# canmultitap.net
KiCad netlist of a schematic drawn in EAGLE
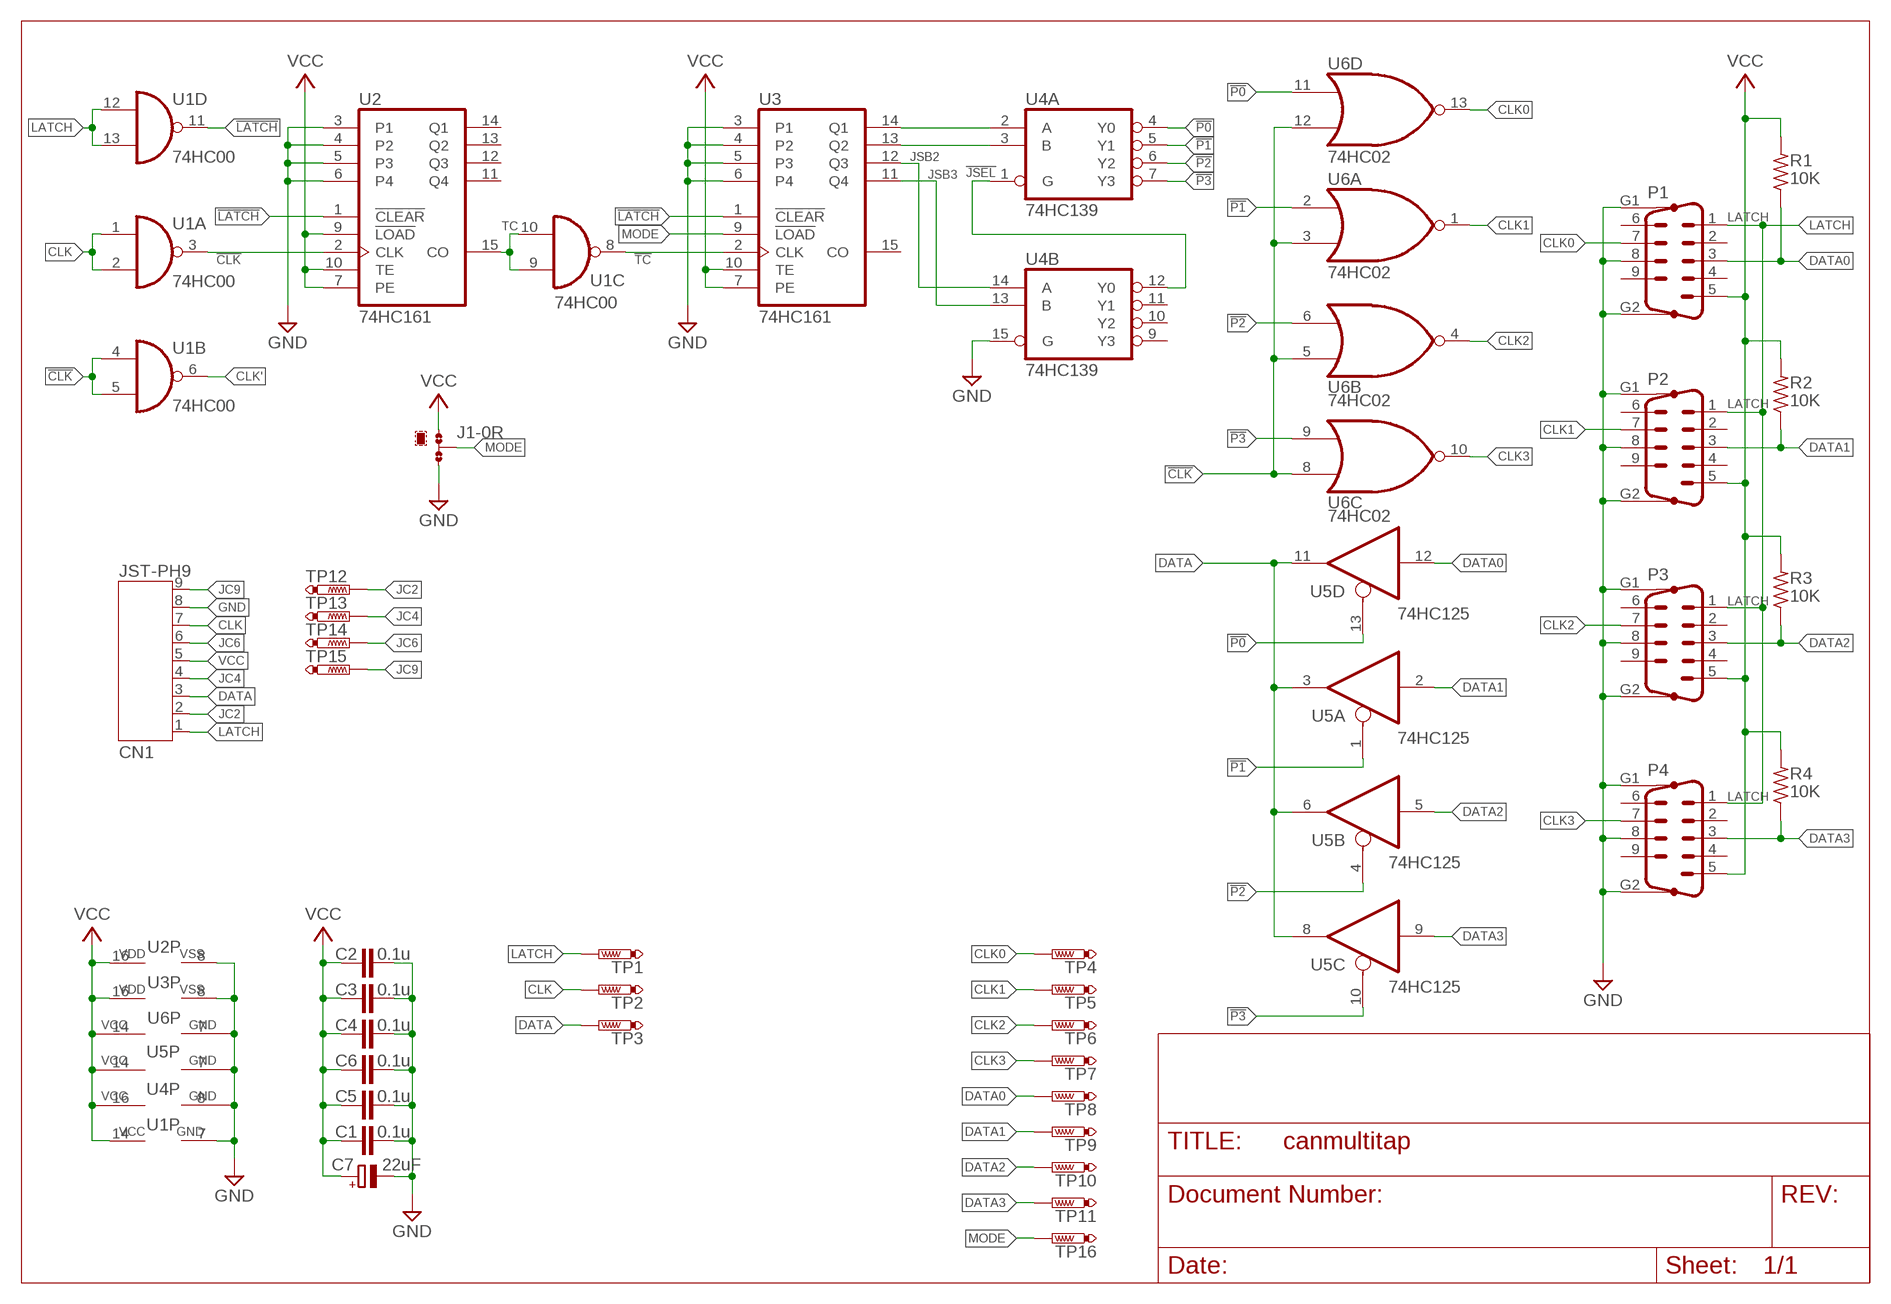
[diagram p0: schematic, sheet 1]

(export (version "E")
  (design (tool "Eeschema 10.0.6"))
  (components
    (comp (ref "C1")
      (value "0.1u")
      (footprint "eagle-import:C0805")
      (libsource (lib "eagle-import") (part "C-EUC0805"))
    )
    (comp (ref "C2")
      (value "0.1u")
      (footprint "eagle-import:C0805")
      (libsource (lib "eagle-import") (part "C-EUC0805"))
    )
    (comp (ref "C3")
      (value "0.1u")
      (footprint "eagle-import:C0805")
      (libsource (lib "eagle-import") (part "C-EUC0805"))
    )
    (comp (ref "C4")
      (value "0.1u")
      (footprint "eagle-import:C0805")
      (libsource (lib "eagle-import") (part "C-EUC0805"))
    )
    (comp (ref "C5")
      (value "0.1u")
      (footprint "eagle-import:C0805")
      (libsource (lib "eagle-import") (part "C-EUC0805"))
    )
    (comp (ref "C6")
      (value "0.1u")
      (footprint "eagle-import:C0805")
      (libsource (lib "eagle-import") (part "C-EUC0805"))
    )
    (comp (ref "C7")
      (value "22uF")
      (footprint "eagle-import:E2-4")
      (libsource (lib "eagle-import") (part "CPOL-EUE2-4"))
    )
    (comp (ref "CN1")
      (value "JST-PH9")
      (footprint "eagle-import:JST-PH9")
      (libsource (lib "eagle-import") (part "JST-PH9"))
    )
    (comp (ref "J1")
      (value "0R-JUMPA")
      (footprint "eagle-import:A0R-JMP")
      (libsource (lib "eagle-import") (part "0R-JUMPA"))
    )
    (comp (ref "P1")
      (value "M09HP")
      (footprint "eagle-import:M09HP")
      (libsource (lib "eagle-import") (part "M09HP"))
    )
    (comp (ref "P2")
      (value "M09HP")
      (footprint "eagle-import:M09HP")
      (libsource (lib "eagle-import") (part "M09HP"))
    )
    (comp (ref "P3")
      (value "M09HP")
      (footprint "eagle-import:M09HP")
      (libsource (lib "eagle-import") (part "M09HP"))
    )
    (comp (ref "P4")
      (value "M09HP")
      (footprint "eagle-import:M09HP")
      (libsource (lib "eagle-import") (part "M09HP"))
    )
    (comp (ref "R1")
      (value "10K")
      (footprint "eagle-import:R0805")
      (libsource (lib "eagle-import") (part "R-US_R0805"))
    )
    (comp (ref "R2")
      (value "10K")
      (footprint "eagle-import:R0805")
      (libsource (lib "eagle-import") (part "R-US_R0805"))
    )
    (comp (ref "R3")
      (value "10K")
      (footprint "eagle-import:R0805")
      (libsource (lib "eagle-import") (part "R-US_R0805"))
    )
    (comp (ref "R4")
      (value "10K")
      (footprint "eagle-import:R0805")
      (libsource (lib "eagle-import") (part "R-US_R0805"))
    )
    (comp (ref "TP1")
      (value "PTR1TP09R")
      (footprint "eagle-import:TP09R")
      (libsource (lib "eagle-import") (part "PTR1TP09R"))
    )
    (comp (ref "TP2")
      (value "PTR1TP09R")
      (footprint "eagle-import:TP09R")
      (libsource (lib "eagle-import") (part "PTR1TP09R"))
    )
    (comp (ref "TP3")
      (value "PTR1TP09R")
      (footprint "eagle-import:TP09R")
      (libsource (lib "eagle-import") (part "PTR1TP09R"))
    )
    (comp (ref "TP4")
      (value "PTR1TP09R")
      (footprint "eagle-import:TP09R")
      (libsource (lib "eagle-import") (part "PTR1TP09R"))
    )
    (comp (ref "TP5")
      (value "PTR1TP09R")
      (footprint "eagle-import:TP09R")
      (libsource (lib "eagle-import") (part "PTR1TP09R"))
    )
    (comp (ref "TP6")
      (value "PTR1TP09R")
      (footprint "eagle-import:TP09R")
      (libsource (lib "eagle-import") (part "PTR1TP09R"))
    )
    (comp (ref "TP7")
      (value "PTR1TP09R")
      (footprint "eagle-import:TP09R")
      (libsource (lib "eagle-import") (part "PTR1TP09R"))
    )
    (comp (ref "TP8")
      (value "PTR1TP09R")
      (footprint "eagle-import:TP09R")
      (libsource (lib "eagle-import") (part "PTR1TP09R"))
    )
    (comp (ref "TP9")
      (value "PTR1TP09R")
      (footprint "eagle-import:TP09R")
      (libsource (lib "eagle-import") (part "PTR1TP09R"))
    )
    (comp (ref "TP10")
      (value "PTR1TP09R")
      (footprint "eagle-import:TP09R")
      (libsource (lib "eagle-import") (part "PTR1TP09R"))
    )
    (comp (ref "TP11")
      (value "PTR1TP09R")
      (footprint "eagle-import:TP09R")
      (libsource (lib "eagle-import") (part "PTR1TP09R"))
    )
    (comp (ref "TP12")
      (value "PTR1TP09R")
      (footprint "eagle-import:TP09R")
      (libsource (lib "eagle-import") (part "PTR1TP09R"))
    )
    (comp (ref "TP13")
      (value "PTR1TP09R")
      (footprint "eagle-import:TP09R")
      (libsource (lib "eagle-import") (part "PTR1TP09R"))
    )
    (comp (ref "TP14")
      (value "PTR1TP09R")
      (footprint "eagle-import:TP09R")
      (libsource (lib "eagle-import") (part "PTR1TP09R"))
    )
    (comp (ref "TP15")
      (value "PTR1TP09R")
      (footprint "eagle-import:TP09R")
      (libsource (lib "eagle-import") (part "PTR1TP09R"))
    )
    (comp (ref "TP16")
      (value "PTR1TP09R")
      (footprint "eagle-import:TP09R")
      (libsource (lib "eagle-import") (part "PTR1TP09R"))
    )
    (comp (ref "U1")
      (value "74HC00")
      (footprint "eagle-import:TSSOP14")
      (libsource (lib "eagle-import") (part "7400PW"))
    )
    (comp (ref "U2")
      (value "74HC161")
      (footprint "eagle-import:TSSOP16")
      (libsource (lib "eagle-import") (part "4161PW"))
    )
    (comp (ref "U3")
      (value "74HC161")
      (footprint "eagle-import:TSSOP16")
      (libsource (lib "eagle-import") (part "4161PW"))
    )
    (comp (ref "U4")
      (value "74HC139")
      (footprint "eagle-import:TSSOP16")
      (libsource (lib "eagle-import") (part "74139PW"))
    )
    (comp (ref "U5")
      (value "74HC125")
      (footprint "eagle-import:TSSOP14")
      (libsource (lib "eagle-import") (part "74125PWABT"))
    )
    (comp (ref "U6")
      (value "74HC02")
      (footprint "eagle-import:TSSOP14")
      (libsource (lib "eagle-import") (part "7402PW"))
    )
  )
  (nets
    (net (code "1") (name "/JSB2") (class "Default")
      (node (ref "U3") (pin "12") (pinfunction "Q3_12") (pintype "output"))
      (node (ref "U4") (pin "14") (pinfunction "A_14") (pintype "input"))
    )
    (net (code "2") (name "/JSB3") (class "Default")
      (node (ref "U3") (pin "11") (pinfunction "Q4_11") (pintype "output"))
      (node (ref "U4") (pin "13") (pinfunction "B_13") (pintype "input"))
    )
    (net (code "3") (name "/TC") (class "Default")
      (node (ref "U1") (pin "10") (pinfunction "I1_10") (pintype "input"))
      (node (ref "U1") (pin "9") (pinfunction "I0_9") (pintype "input"))
      (node (ref "U2") (pin "15") (pinfunction "CO_15") (pintype "output"))
    )
    (net (code "4") (name "/~{CLK}") (class "Default")
      (node (ref "U1") (pin "3") (pinfunction "O_3") (pintype "output"))
      (node (ref "U1") (pin "4") (pinfunction "I0_4") (pintype "input"))
      (node (ref "U1") (pin "5") (pinfunction "I1_5") (pintype "input"))
      (node (ref "U2") (pin "2") (pinfunction "CLK_2") (pintype "input"))
      (node (ref "U6") (pin "12") (pinfunction "I1_12") (pintype "input"))
      (node (ref "U6") (pin "3") (pinfunction "I1_3") (pintype "input"))
      (node (ref "U6") (pin "5") (pinfunction "I0_5") (pintype "input"))
      (node (ref "U6") (pin "8") (pinfunction "I0_8") (pintype "input"))
    )
    (net (code "5") (name "/~{JSEL}") (class "Default")
      (node (ref "U4") (pin "1") (pinfunction "G_1") (pintype "input"))
      (node (ref "U4") (pin "12") (pinfunction "Y0_12") (pintype "output"))
    )
    (net (code "6") (name "/~{LATCH}") (class "Default")
      (node (ref "U1") (pin "11") (pinfunction "O_11") (pintype "output"))
      (node (ref "U2") (pin "1") (pinfunction "~{CLEAR}_1") (pintype "input"))
      (node (ref "U3") (pin "1") (pinfunction "~{CLEAR}_1") (pintype "input"))
    )
    (net (code "7") (name "/~{P0}") (class "Default")
      (node (ref "U4") (pin "4") (pinfunction "Y0_4") (pintype "output"))
      (node (ref "U5") (pin "13") (pinfunction "OE_13") (pintype "input"))
      (node (ref "U6") (pin "11") (pinfunction "I0_11") (pintype "input"))
    )
    (net (code "8") (name "/~{P1}") (class "Default")
      (node (ref "U4") (pin "5") (pinfunction "Y1_5") (pintype "output"))
      (node (ref "U5") (pin "1") (pinfunction "OE_1") (pintype "input"))
      (node (ref "U6") (pin "2") (pinfunction "I0_2") (pintype "input"))
    )
    (net (code "9") (name "/~{P2}") (class "Default")
      (node (ref "U4") (pin "6") (pinfunction "Y2_6") (pintype "output"))
      (node (ref "U5") (pin "4") (pinfunction "OE_4") (pintype "input"))
      (node (ref "U6") (pin "6") (pinfunction "I1_6") (pintype "input"))
    )
    (net (code "10") (name "/~{P3}") (class "Default")
      (node (ref "U4") (pin "7") (pinfunction "Y3_7") (pintype "output"))
      (node (ref "U5") (pin "10") (pinfunction "OE_10") (pintype "input"))
      (node (ref "U6") (pin "9") (pinfunction "I1_9") (pintype "input"))
    )
    (net (code "11") (name "/~{TC}") (class "Default")
      (node (ref "U1") (pin "8") (pinfunction "O_8") (pintype "output"))
      (node (ref "U3") (pin "2") (pinfunction "CLK_2") (pintype "input"))
    )
    (net (code "12") (name "CLK") (class "Default")
      (node (ref "CN1") (pin "7") (pinfunction "7_7") (pintype "passive"))
      (node (ref "TP2") (pin "TP") (pinfunction "TP_TP") (pintype "input"))
      (node (ref "U1") (pin "1") (pinfunction "I0_1") (pintype "input"))
      (node (ref "U1") (pin "2") (pinfunction "I1_2") (pintype "input"))
    )
    (net (code "13") (name "CLK'") (class "Default")
      (node (ref "U1") (pin "6") (pinfunction "O_6") (pintype "output"))
    )
    (net (code "14") (name "CLK0") (class "Default")
      (node (ref "P1") (pin "7") (pinfunction "7_7") (pintype "passive"))
      (node (ref "TP4") (pin "TP") (pinfunction "TP_TP") (pintype "input"))
      (node (ref "U6") (pin "13") (pinfunction "O_13") (pintype "output"))
    )
    (net (code "15") (name "CLK1") (class "Default")
      (node (ref "P2") (pin "7") (pinfunction "7_7") (pintype "passive"))
      (node (ref "TP5") (pin "TP") (pinfunction "TP_TP") (pintype "input"))
      (node (ref "U6") (pin "1") (pinfunction "O_1") (pintype "output"))
    )
    (net (code "16") (name "CLK2") (class "Default")
      (node (ref "P3") (pin "7") (pinfunction "7_7") (pintype "passive"))
      (node (ref "TP6") (pin "TP") (pinfunction "TP_TP") (pintype "input"))
      (node (ref "U6") (pin "4") (pinfunction "O_4") (pintype "output"))
    )
    (net (code "17") (name "CLK3") (class "Default")
      (node (ref "P4") (pin "7") (pinfunction "7_7") (pintype "passive"))
      (node (ref "TP7") (pin "TP") (pinfunction "TP_TP") (pintype "input"))
      (node (ref "U6") (pin "10") (pinfunction "O_10") (pintype "output"))
    )
    (net (code "18") (name "DATA") (class "Default")
      (node (ref "CN1") (pin "3") (pinfunction "3_3") (pintype "passive"))
      (node (ref "TP3") (pin "TP") (pinfunction "TP_TP") (pintype "input"))
      (node (ref "U5") (pin "11") (pinfunction "O_11") (pintype "tri_state"))
      (node (ref "U5") (pin "3") (pinfunction "O_3") (pintype "tri_state"))
      (node (ref "U5") (pin "6") (pinfunction "O_6") (pintype "tri_state"))
      (node (ref "U5") (pin "8") (pinfunction "O_8") (pintype "tri_state"))
    )
    (net (code "19") (name "DATA0") (class "Default")
      (node (ref "P1") (pin "3") (pinfunction "3_3") (pintype "passive"))
      (node (ref "R1") (pin "1") (pinfunction "1_1") (pintype "passive"))
      (node (ref "TP8") (pin "TP") (pinfunction "TP_TP") (pintype "input"))
      (node (ref "U5") (pin "12") (pinfunction "I_12") (pintype "input"))
    )
    (net (code "20") (name "DATA1") (class "Default")
      (node (ref "P2") (pin "3") (pinfunction "3_3") (pintype "passive"))
      (node (ref "R2") (pin "1") (pinfunction "1_1") (pintype "passive"))
      (node (ref "TP9") (pin "TP") (pinfunction "TP_TP") (pintype "input"))
      (node (ref "U5") (pin "2") (pinfunction "I_2") (pintype "input"))
    )
    (net (code "21") (name "DATA2") (class "Default")
      (node (ref "P3") (pin "3") (pinfunction "3_3") (pintype "passive"))
      (node (ref "R3") (pin "1") (pinfunction "1_1") (pintype "passive"))
      (node (ref "TP10") (pin "TP") (pinfunction "TP_TP") (pintype "input"))
      (node (ref "U5") (pin "5") (pinfunction "I_5") (pintype "input"))
    )
    (net (code "22") (name "DATA3") (class "Default")
      (node (ref "P4") (pin "3") (pinfunction "3_3") (pintype "passive"))
      (node (ref "R4") (pin "1") (pinfunction "1_1") (pintype "passive"))
      (node (ref "TP11") (pin "TP") (pinfunction "TP_TP") (pintype "input"))
      (node (ref "U5") (pin "9") (pinfunction "I_9") (pintype "input"))
    )
    (net (code "23") (name "GND") (class "Default")
      (node (ref "C1") (pin "2") (pinfunction "2_2") (pintype "passive"))
      (node (ref "C2") (pin "2") (pinfunction "2_2") (pintype "passive"))
      (node (ref "C3") (pin "2") (pinfunction "2_2") (pintype "passive"))
      (node (ref "C4") (pin "2") (pinfunction "2_2") (pintype "passive"))
      (node (ref "C5") (pin "2") (pinfunction "2_2") (pintype "passive"))
      (node (ref "C6") (pin "2") (pinfunction "2_2") (pintype "passive"))
      (node (ref "C7") (pin "-") (pinfunction "-_-") (pintype "passive"))
      (node (ref "CN1") (pin "8") (pinfunction "8_8") (pintype "passive"))
      (node (ref "J1") (pin "3") (pinfunction "3_3") (pintype "passive"))
      (node (ref "P1") (pin "8") (pinfunction "8_8") (pintype "passive"))
      (node (ref "P1") (pin "G1") (pinfunction "G1_G1") (pintype "passive"))
      (node (ref "P1") (pin "G2") (pinfunction "G2_G2") (pintype "passive"))
      (node (ref "P2") (pin "8") (pinfunction "8_8") (pintype "passive"))
      (node (ref "P2") (pin "G1") (pinfunction "G1_G1") (pintype "passive"))
      (node (ref "P2") (pin "G2") (pinfunction "G2_G2") (pintype "passive"))
      (node (ref "P3") (pin "8") (pinfunction "8_8") (pintype "passive"))
      (node (ref "P3") (pin "G1") (pinfunction "G1_G1") (pintype "passive"))
      (node (ref "P3") (pin "G2") (pinfunction "G2_G2") (pintype "passive"))
      (node (ref "P4") (pin "8") (pinfunction "8_8") (pintype "passive"))
      (node (ref "P4") (pin "G1") (pinfunction "G1_G1") (pintype "passive"))
      (node (ref "P4") (pin "G2") (pinfunction "G2_G2") (pintype "passive"))
      (node (ref "U1") (pin "7") (pinfunction "GND_7") (pintype "power_in"))
      (node (ref "U2") (pin "3") (pinfunction "P1_3") (pintype "input"))
      (node (ref "U2") (pin "4") (pinfunction "P2_4") (pintype "input"))
      (node (ref "U2") (pin "5") (pinfunction "P3_5") (pintype "input"))
      (node (ref "U2") (pin "6") (pinfunction "P4_6") (pintype "input"))
      (node (ref "U2") (pin "8") (pinfunction "VSS_8") (pintype "power_in"))
      (node (ref "U3") (pin "3") (pinfunction "P1_3") (pintype "input"))
      (node (ref "U3") (pin "4") (pinfunction "P2_4") (pintype "input"))
      (node (ref "U3") (pin "5") (pinfunction "P3_5") (pintype "input"))
      (node (ref "U3") (pin "6") (pinfunction "P4_6") (pintype "input"))
      (node (ref "U3") (pin "8") (pinfunction "VSS_8") (pintype "power_in"))
      (node (ref "U4") (pin "15") (pinfunction "G_15") (pintype "input"))
      (node (ref "U4") (pin "8") (pinfunction "GND_8") (pintype "power_in"))
      (node (ref "U5") (pin "7") (pinfunction "GND_7") (pintype "power_in"))
      (node (ref "U6") (pin "7") (pinfunction "GND_7") (pintype "power_in"))
    )
    (net (code "24") (name "JC2") (class "Default")
      (node (ref "CN1") (pin "2") (pinfunction "2_2") (pintype "passive"))
      (node (ref "TP12") (pin "TP") (pinfunction "TP_TP") (pintype "input"))
    )
    (net (code "25") (name "JC4") (class "Default")
      (node (ref "CN1") (pin "4") (pinfunction "4_4") (pintype "passive"))
      (node (ref "TP13") (pin "TP") (pinfunction "TP_TP") (pintype "input"))
    )
    (net (code "26") (name "JC6") (class "Default")
      (node (ref "CN1") (pin "6") (pinfunction "6_6") (pintype "passive"))
      (node (ref "TP14") (pin "TP") (pinfunction "TP_TP") (pintype "input"))
    )
    (net (code "27") (name "JC9") (class "Default")
      (node (ref "CN1") (pin "9") (pinfunction "9_9") (pintype "passive"))
      (node (ref "TP15") (pin "TP") (pinfunction "TP_TP") (pintype "input"))
    )
    (net (code "28") (name "LATCH") (class "Default")
      (node (ref "CN1") (pin "1") (pinfunction "1_1") (pintype "passive"))
      (node (ref "P1") (pin "1") (pinfunction "1_1") (pintype "passive"))
      (node (ref "P2") (pin "1") (pinfunction "1_1") (pintype "passive"))
      (node (ref "P3") (pin "1") (pinfunction "1_1") (pintype "passive"))
      (node (ref "P4") (pin "1") (pinfunction "1_1") (pintype "passive"))
      (node (ref "TP1") (pin "TP") (pinfunction "TP_TP") (pintype "input"))
      (node (ref "U1") (pin "12") (pinfunction "I0_12") (pintype "input"))
      (node (ref "U1") (pin "13") (pinfunction "I1_13") (pintype "input"))
    )
    (net (code "29") (name "MODE") (class "Default")
      (node (ref "J1") (pin "2") (pinfunction "2_2") (pintype "passive"))
      (node (ref "TP16") (pin "TP") (pinfunction "TP_TP") (pintype "input"))
      (node (ref "U3") (pin "9") (pinfunction "~{LOAD}_9") (pintype "input"))
    )
    (net (code "30") (name "Net-(U3A-Q1)") (class "Default")
      (node (ref "U3") (pin "14") (pinfunction "Q1_14") (pintype "output"))
      (node (ref "U4") (pin "2") (pinfunction "A_2") (pintype "input"))
    )
    (net (code "31") (name "Net-(U3A-Q2)") (class "Default")
      (node (ref "U3") (pin "13") (pinfunction "Q2_13") (pintype "output"))
      (node (ref "U4") (pin "3") (pinfunction "B_3") (pintype "input"))
    )
    (net (code "32") (name "VCC") (class "Default")
      (node (ref "C1") (pin "1") (pinfunction "1_1") (pintype "passive"))
      (node (ref "C2") (pin "1") (pinfunction "1_1") (pintype "passive"))
      (node (ref "C3") (pin "1") (pinfunction "1_1") (pintype "passive"))
      (node (ref "C4") (pin "1") (pinfunction "1_1") (pintype "passive"))
      (node (ref "C5") (pin "1") (pinfunction "1_1") (pintype "passive"))
      (node (ref "C6") (pin "1") (pinfunction "1_1") (pintype "passive"))
      (node (ref "C7") (pin "+") (pinfunction "+_+") (pintype "passive"))
      (node (ref "CN1") (pin "5") (pinfunction "5_5") (pintype "passive"))
      (node (ref "J1") (pin "1") (pinfunction "1_1") (pintype "passive"))
      (node (ref "P1") (pin "5") (pinfunction "5_5") (pintype "passive"))
      (node (ref "P2") (pin "5") (pinfunction "5_5") (pintype "passive"))
      (node (ref "P3") (pin "5") (pinfunction "5_5") (pintype "passive"))
      (node (ref "P4") (pin "5") (pinfunction "5_5") (pintype "passive"))
      (node (ref "R1") (pin "2") (pinfunction "2_2") (pintype "passive"))
      (node (ref "R2") (pin "2") (pinfunction "2_2") (pintype "passive"))
      (node (ref "R3") (pin "2") (pinfunction "2_2") (pintype "passive"))
      (node (ref "R4") (pin "2") (pinfunction "2_2") (pintype "passive"))
      (node (ref "U1") (pin "14") (pinfunction "VCC_14") (pintype "power_in"))
      (node (ref "U2") (pin "10") (pinfunction "TE_10") (pintype "input"))
      (node (ref "U2") (pin "16") (pinfunction "VDD_16") (pintype "power_in"))
      (node (ref "U2") (pin "7") (pinfunction "PE_7") (pintype "input"))
      (node (ref "U2") (pin "9") (pinfunction "~{LOAD}_9") (pintype "input"))
      (node (ref "U3") (pin "10") (pinfunction "TE_10") (pintype "input"))
      (node (ref "U3") (pin "16") (pinfunction "VDD_16") (pintype "power_in"))
      (node (ref "U3") (pin "7") (pinfunction "PE_7") (pintype "input"))
      (node (ref "U4") (pin "16") (pinfunction "VCC_16") (pintype "power_in"))
      (node (ref "U5") (pin "14") (pinfunction "VCC_14") (pintype "power_in"))
      (node (ref "U6") (pin "14") (pinfunction "VCC_14") (pintype "power_in"))
    )
    (net (code "33") (name "unconnected-(P1-Pad2)") (class "Default")
      (node (ref "P1") (pin "2") (pinfunction "2_2") (pintype "passive"))
    )
    (net (code "34") (name "unconnected-(P1-Pad4)") (class "Default")
      (node (ref "P1") (pin "4") (pinfunction "4_4") (pintype "passive"))
    )
    (net (code "35") (name "unconnected-(P1-Pad6)") (class "Default")
      (node (ref "P1") (pin "6") (pinfunction "6_6") (pintype "passive"))
    )
    (net (code "36") (name "unconnected-(P1-Pad9)") (class "Default")
      (node (ref "P1") (pin "9") (pinfunction "9_9") (pintype "passive"))
    )
    (net (code "37") (name "unconnected-(P2-Pad2)") (class "Default")
      (node (ref "P2") (pin "2") (pinfunction "2_2") (pintype "passive"))
    )
    (net (code "38") (name "unconnected-(P2-Pad4)") (class "Default")
      (node (ref "P2") (pin "4") (pinfunction "4_4") (pintype "passive"))
    )
    (net (code "39") (name "unconnected-(P2-Pad6)") (class "Default")
      (node (ref "P2") (pin "6") (pinfunction "6_6") (pintype "passive"))
    )
    (net (code "40") (name "unconnected-(P2-Pad9)") (class "Default")
      (node (ref "P2") (pin "9") (pinfunction "9_9") (pintype "passive"))
    )
    (net (code "41") (name "unconnected-(P3-Pad2)") (class "Default")
      (node (ref "P3") (pin "2") (pinfunction "2_2") (pintype "passive"))
    )
    (net (code "42") (name "unconnected-(P3-Pad4)") (class "Default")
      (node (ref "P3") (pin "4") (pinfunction "4_4") (pintype "passive"))
    )
    (net (code "43") (name "unconnected-(P3-Pad6)") (class "Default")
      (node (ref "P3") (pin "6") (pinfunction "6_6") (pintype "passive"))
    )
    (net (code "44") (name "unconnected-(P3-Pad9)") (class "Default")
      (node (ref "P3") (pin "9") (pinfunction "9_9") (pintype "passive"))
    )
    (net (code "45") (name "unconnected-(P4-Pad2)") (class "Default")
      (node (ref "P4") (pin "2") (pinfunction "2_2") (pintype "passive"))
    )
    (net (code "46") (name "unconnected-(P4-Pad4)") (class "Default")
      (node (ref "P4") (pin "4") (pinfunction "4_4") (pintype "passive"))
    )
    (net (code "47") (name "unconnected-(P4-Pad6)") (class "Default")
      (node (ref "P4") (pin "6") (pinfunction "6_6") (pintype "passive"))
    )
    (net (code "48") (name "unconnected-(P4-Pad9)") (class "Default")
      (node (ref "P4") (pin "9") (pinfunction "9_9") (pintype "passive"))
    )
    (net (code "49") (name "unconnected-(U2A-Q1-Pad14)") (class "Default")
      (node (ref "U2") (pin "14") (pinfunction "Q1_14") (pintype "output"))
    )
    (net (code "50") (name "unconnected-(U2A-Q2-Pad13)") (class "Default")
      (node (ref "U2") (pin "13") (pinfunction "Q2_13") (pintype "output"))
    )
    (net (code "51") (name "unconnected-(U2A-Q3-Pad12)") (class "Default")
      (node (ref "U2") (pin "12") (pinfunction "Q3_12") (pintype "output"))
    )
    (net (code "52") (name "unconnected-(U2A-Q4-Pad11)") (class "Default")
      (node (ref "U2") (pin "11") (pinfunction "Q4_11") (pintype "output"))
    )
    (net (code "53") (name "unconnected-(U3A-CO-Pad15)") (class "Default")
      (node (ref "U3") (pin "15") (pinfunction "CO_15") (pintype "output"))
    )
    (net (code "54") (name "unconnected-(U4B-Y1-Pad11)") (class "Default")
      (node (ref "U4") (pin "11") (pinfunction "Y1_11") (pintype "output"))
    )
    (net (code "55") (name "unconnected-(U4B-Y2-Pad10)") (class "Default")
      (node (ref "U4") (pin "10") (pinfunction "Y2_10") (pintype "output"))
    )
    (net (code "56") (name "unconnected-(U4B-Y3-Pad9)") (class "Default")
      (node (ref "U4") (pin "9") (pinfunction "Y3_9") (pintype "output"))
    )
  )
)
